# RPi-ShieldBridge_v11.net
KiCad netlist of a schematic drawn in EAGLE
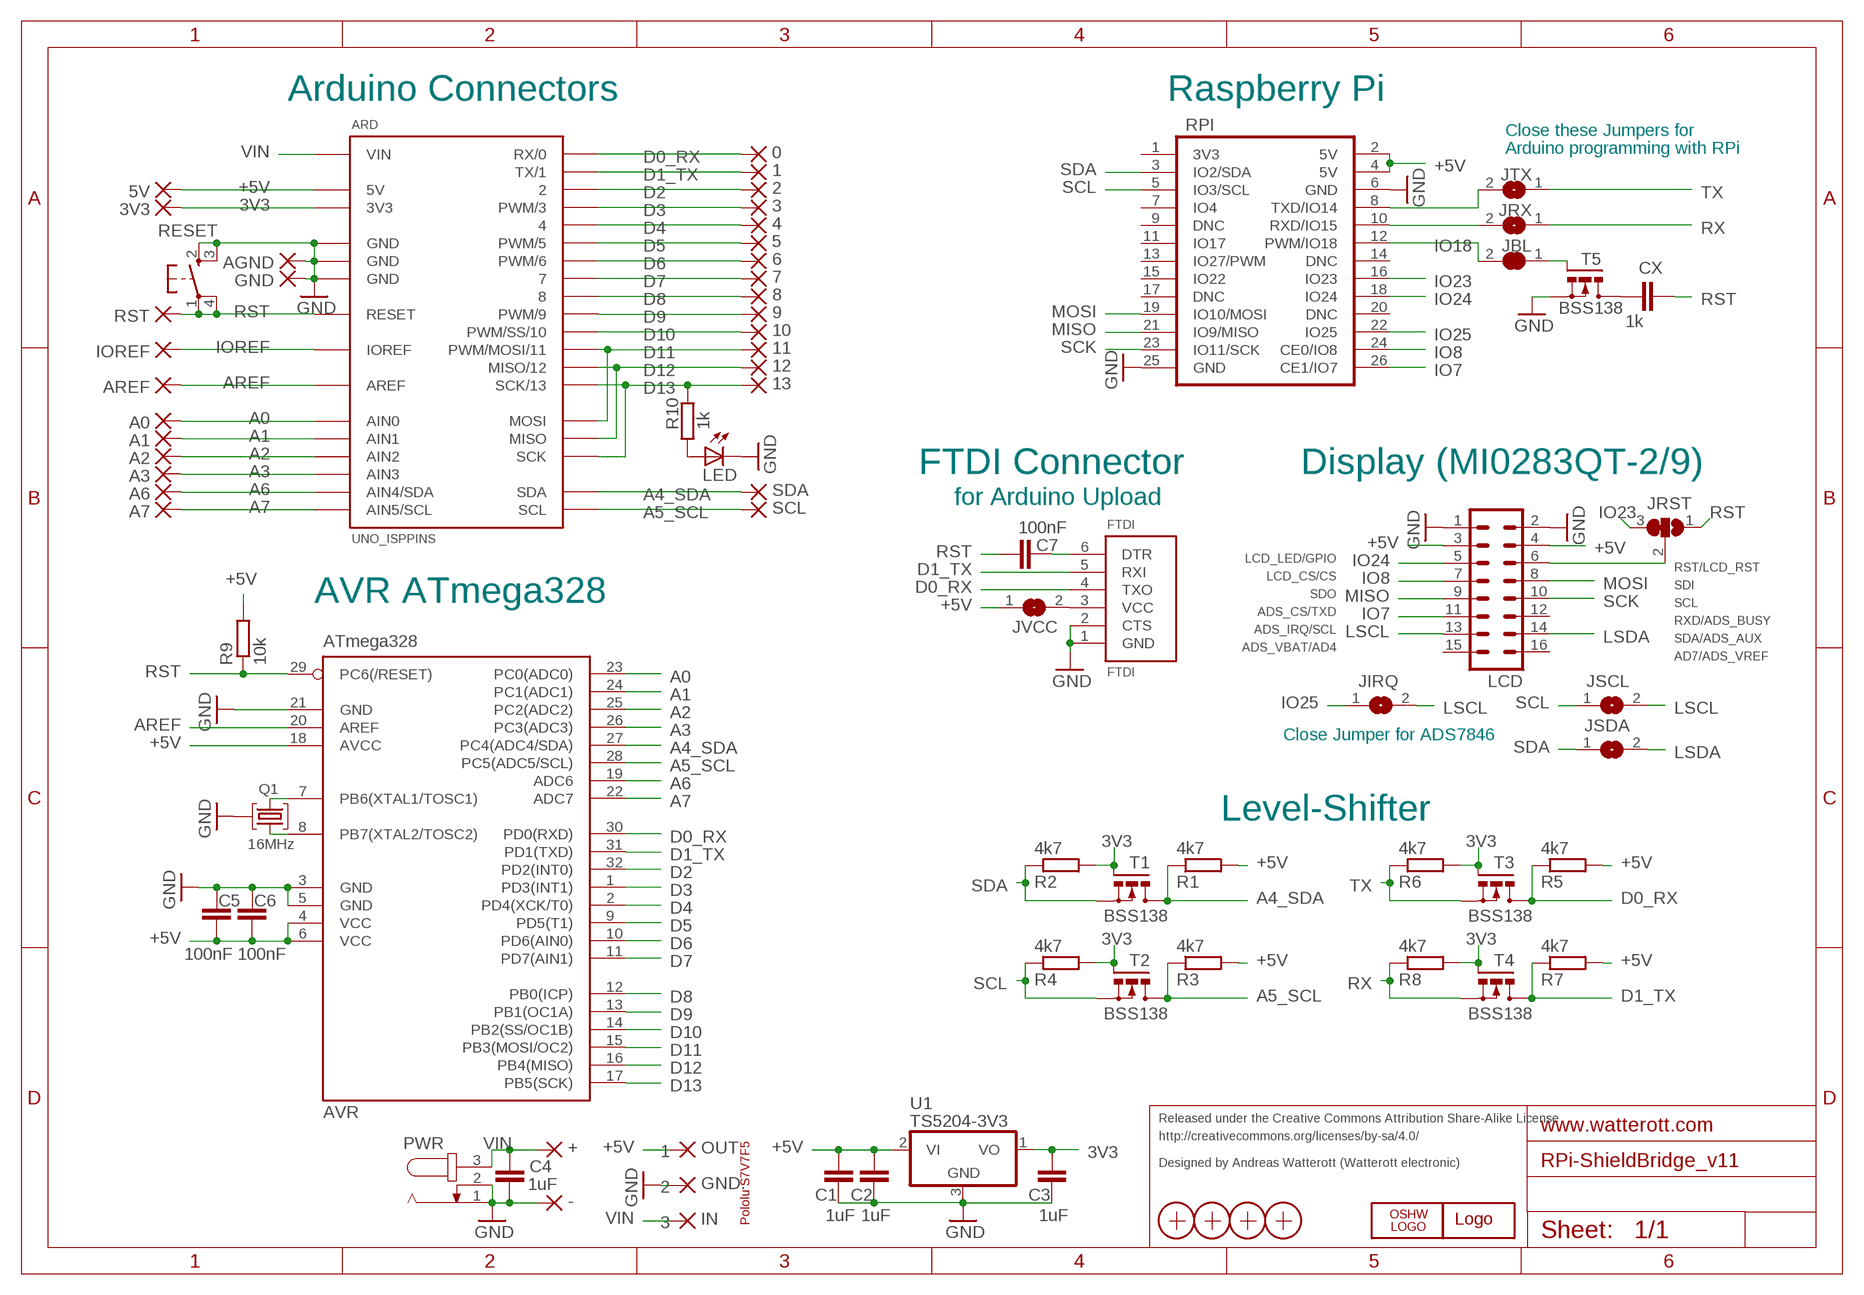
[diagram p0: schematic, sheet 1]

(export (version "E")
  (design (tool "Eeschema 10.0.6"))
  (components
    (comp (ref "+")
      (value "WIREPAD2,54/1,0")
      (footprint "eagle-import:2,54_1,0")
      (libsource (lib "eagle-import") (part "WIREPAD2,54/1,0"))
    )
    (comp (ref "-")
      (value "WIREPAD2,54/1,0")
      (footprint "eagle-import:2,54_1,0")
      (libsource (lib "eagle-import") (part "WIREPAD2,54/1,0"))
    )
    (comp (ref "0")
      (value "WIREPAD1,6/0,9")
      (footprint "eagle-import:1,6_0,9")
      (libsource (lib "eagle-import") (part "WIREPAD1,6/0,9"))
    )
    (comp (ref "1")
      (value "WIREPAD1,6/0,9")
      (footprint "eagle-import:1,6_0,9")
      (libsource (lib "eagle-import") (part "WIREPAD1,6/0,9"))
    )
    (comp (ref "2")
      (value "WIREPAD1,6/0,9")
      (footprint "eagle-import:1,6_0,9")
      (libsource (lib "eagle-import") (part "WIREPAD1,6/0,9"))
    )
    (comp (ref "3")
      (value "WIREPAD1,6/0,9")
      (footprint "eagle-import:1,6_0,9")
      (libsource (lib "eagle-import") (part "WIREPAD1,6/0,9"))
    )
    (comp (ref "3V3")
      (value "WIREPAD1,6/0,9")
      (footprint "eagle-import:1,6_0,9")
      (libsource (lib "eagle-import") (part "WIREPAD1,6/0,9"))
    )
    (comp (ref "4")
      (value "WIREPAD1,6/0,9")
      (footprint "eagle-import:1,6_0,9")
      (libsource (lib "eagle-import") (part "WIREPAD1,6/0,9"))
    )
    (comp (ref "5")
      (value "WIREPAD1,6/0,9")
      (footprint "eagle-import:1,6_0,9")
      (libsource (lib "eagle-import") (part "WIREPAD1,6/0,9"))
    )
    (comp (ref "5V")
      (value "WIREPAD1,6/0,9")
      (footprint "eagle-import:1,6_0,9")
      (libsource (lib "eagle-import") (part "WIREPAD1,6/0,9"))
    )
    (comp (ref "6")
      (value "WIREPAD1,6/0,9")
      (footprint "eagle-import:1,6_0,9")
      (libsource (lib "eagle-import") (part "WIREPAD1,6/0,9"))
    )
    (comp (ref "7")
      (value "WIREPAD1,6/0,9")
      (footprint "eagle-import:1,6_0,9")
      (libsource (lib "eagle-import") (part "WIREPAD1,6/0,9"))
    )
    (comp (ref "8")
      (value "WIREPAD1,6/0,9")
      (footprint "eagle-import:1,6_0,9")
      (libsource (lib "eagle-import") (part "WIREPAD1,6/0,9"))
    )
    (comp (ref "9")
      (value "WIREPAD1,6/0,9")
      (footprint "eagle-import:1,6_0,9")
      (libsource (lib "eagle-import") (part "WIREPAD1,6/0,9"))
    )
    (comp (ref "10")
      (value "WIREPAD1,6/0,9")
      (footprint "eagle-import:1,6_0,9")
      (libsource (lib "eagle-import") (part "WIREPAD1,6/0,9"))
    )
    (comp (ref "11")
      (value "WIREPAD1,6/0,9")
      (footprint "eagle-import:1,6_0,9")
      (libsource (lib "eagle-import") (part "WIREPAD1,6/0,9"))
    )
    (comp (ref "12")
      (value "WIREPAD1,6/0,9")
      (footprint "eagle-import:1,6_0,9")
      (libsource (lib "eagle-import") (part "WIREPAD1,6/0,9"))
    )
    (comp (ref "13")
      (value "WIREPAD1,6/0,9")
      (footprint "eagle-import:1,6_0,9")
      (libsource (lib "eagle-import") (part "WIREPAD1,6/0,9"))
    )
    (comp (ref "A0")
      (value "WIREPAD1,6/0,9")
      (footprint "eagle-import:1,6_0,9")
      (libsource (lib "eagle-import") (part "WIREPAD1,6/0,9"))
    )
    (comp (ref "A1")
      (value "WIREPAD1,6/0,9")
      (footprint "eagle-import:1,6_0,9")
      (libsource (lib "eagle-import") (part "WIREPAD1,6/0,9"))
    )
    (comp (ref "A2")
      (value "WIREPAD1,6/0,9")
      (footprint "eagle-import:1,6_0,9")
      (libsource (lib "eagle-import") (part "WIREPAD1,6/0,9"))
    )
    (comp (ref "A3")
      (value "WIREPAD1,6/0,9")
      (footprint "eagle-import:1,6_0,9")
      (libsource (lib "eagle-import") (part "WIREPAD1,6/0,9"))
    )
    (comp (ref "A6")
      (value "WIREPAD1,6/0,9")
      (footprint "eagle-import:1,6_0,9")
      (libsource (lib "eagle-import") (part "WIREPAD1,6/0,9"))
    )
    (comp (ref "A7")
      (value "WIREPAD1,6/0,9")
      (footprint "eagle-import:1,6_0,9")
      (libsource (lib "eagle-import") (part "WIREPAD1,6/0,9"))
    )
    (comp (ref "AGND")
      (value "WIREPAD1,6/0,9")
      (footprint "eagle-import:1,6_0,9")
      (libsource (lib "eagle-import") (part "WIREPAD1,6/0,9"))
    )
    (comp (ref "ARD")
      (value "UNO_ISPPINS")
      (footprint "eagle-import:UNO_ISP3")
      (libsource (lib "eagle-import") (part "UNO_ISPPINS"))
    )
    (comp (ref "AREF")
      (value "WIREPAD1,6/0,9")
      (footprint "eagle-import:1,6_0,9")
      (libsource (lib "eagle-import") (part "WIREPAD1,6/0,9"))
    )
    (comp (ref "AVR")
      (value "ATmega328")
      (footprint "eagle-import:TQFP32-08")
      (fields (field (name "MPN") "ATMEGA8-16AU"))
      (libsource (lib "eagle-import") (part "MEGA8-AI"))
    )
    (comp (ref "C1")
      (value "1uF")
      (footprint "eagle-import:C0603")
      (libsource (lib "eagle-import") (part "C-EUC0603"))
    )
    (comp (ref "C2")
      (value "1uF")
      (footprint "eagle-import:C0603")
      (libsource (lib "eagle-import") (part "C-EUC0603"))
    )
    (comp (ref "C3")
      (value "1uF")
      (footprint "eagle-import:C0603")
      (libsource (lib "eagle-import") (part "C-EUC0603"))
    )
    (comp (ref "C4")
      (value "1uF")
      (footprint "eagle-import:C0603")
      (libsource (lib "eagle-import") (part "C-EUC0603"))
    )
    (comp (ref "C5")
      (value "100nF")
      (footprint "eagle-import:C0603")
      (libsource (lib "eagle-import") (part "C-EUC0603"))
    )
    (comp (ref "C6")
      (value "100nF")
      (footprint "eagle-import:C0603")
      (libsource (lib "eagle-import") (part "C-EUC0603"))
    )
    (comp (ref "C7")
      (value "100nF")
      (footprint "eagle-import:C0603")
      (libsource (lib "eagle-import") (part "C-EUC0603"))
    )
    (comp (ref "CX")
      (value "1k")
      (footprint "eagle-import:C0603")
      (libsource (lib "eagle-import") (part "C-EUC0603"))
    )
    (comp (ref "FTDI")
      (value "FTDI")
      (footprint "eagle-import:FTDI")
      (libsource (lib "eagle-import") (part "FTDI"))
    )
    (comp (ref "GND")
      (value "WIREPAD1,6/0,9")
      (footprint "eagle-import:1,6_0,9")
      (libsource (lib "eagle-import") (part "WIREPAD1,6/0,9"))
    )
    (comp (ref "GND.")
      (value "2")
      (footprint "eagle-import:1,6_0,9")
      (libsource (lib "eagle-import") (part "WIREPAD1,6/0,9"))
    )
    (comp (ref "IN")
      (value "3")
      (footprint "eagle-import:1,6_0,9")
      (libsource (lib "eagle-import") (part "WIREPAD1,6/0,9"))
    )
    (comp (ref "IOREF")
      (value "WIREPAD1,6/0,9")
      (footprint "eagle-import:1,6_0,9")
      (libsource (lib "eagle-import") (part "WIREPAD1,6/0,9"))
    )
    (comp (ref "JBL") (value "SJ") (footprint "eagle-import:SJ") (libsource (lib "eagle-import") (part "SJ")))
    (comp (ref "JIRQ")
      (value "SJ")
      (footprint "eagle-import:SJ")
      (libsource (lib "eagle-import") (part "SJ"))
    )
    (comp (ref "JRST")
      (value "SJ2W")
      (footprint "eagle-import:SJ_2")
      (libsource (lib "eagle-import") (part "SJ2W"))
    )
    (comp (ref "JRX") (value "SJ") (footprint "eagle-import:SJ") (libsource (lib "eagle-import") (part "SJ")))
    (comp (ref "JSCL")
      (value "SJ")
      (footprint "eagle-import:SJ")
      (libsource (lib "eagle-import") (part "SJ"))
    )
    (comp (ref "JSDA")
      (value "SJ")
      (footprint "eagle-import:SJ")
      (libsource (lib "eagle-import") (part "SJ"))
    )
    (comp (ref "JTX") (value "SJ") (footprint "eagle-import:SJ") (libsource (lib "eagle-import") (part "SJ")))
    (comp (ref "JVCC")
      (value "SJ")
      (footprint "eagle-import:SJ")
      (libsource (lib "eagle-import") (part "SJ"))
    )
    (comp (ref "LCD")
      (value "MA08-2")
      (footprint "eagle-import:MA08-2")
      (libsource (lib "eagle-import") (part "MA08-2"))
    )
    (comp (ref "LED")
      (value "LEDCHIPLED_0603")
      (footprint "eagle-import:CHIPLED_0603")
      (libsource (lib "eagle-import") (part "LEDCHIPLED_0603"))
    )
    (comp (ref "LOGO1")
      (value "OSHW_LOGO_6MILX0150-NT")
      (footprint "eagle-import:OSHW_6X150_NOTEXT")
      (libsource (lib "eagle-import") (part "OSHW_LOGO_6MILX0150-NT"))
    )
    (comp (ref "OUT")
      (value "1")
      (footprint "eagle-import:1,6_0,9")
      (libsource (lib "eagle-import") (part "WIREPAD1,6/0,9"))
    )
    (comp (ref "PWR")
      (value "DC-JACK\"\"")
      (footprint "eagle-import:DC-JACK")
      (libsource (lib "eagle-import") (part "DC-JACK{dblquote}{dblquote}"))
    )
    (comp (ref "Q1")
      (value "16MHz")
      (footprint "eagle-import:SMD_OSC_35X15")
      (libsource (lib "eagle-import") (part "SMD_OSC2"))
    )
    (comp (ref "R1")
      (value "4k7")
      (footprint "eagle-import:R0603")
      (libsource (lib "eagle-import") (part "R-EU_R0603"))
    )
    (comp (ref "R2")
      (value "4k7")
      (footprint "eagle-import:R0603")
      (libsource (lib "eagle-import") (part "R-EU_R0603"))
    )
    (comp (ref "R3")
      (value "4k7")
      (footprint "eagle-import:R0603")
      (libsource (lib "eagle-import") (part "R-EU_R0603"))
    )
    (comp (ref "R4")
      (value "4k7")
      (footprint "eagle-import:R0603")
      (libsource (lib "eagle-import") (part "R-EU_R0603"))
    )
    (comp (ref "R5")
      (value "4k7")
      (footprint "eagle-import:R0603")
      (libsource (lib "eagle-import") (part "R-EU_R0603"))
    )
    (comp (ref "R6")
      (value "4k7")
      (footprint "eagle-import:R0603")
      (libsource (lib "eagle-import") (part "R-EU_R0603"))
    )
    (comp (ref "R7")
      (value "4k7")
      (footprint "eagle-import:R0603")
      (libsource (lib "eagle-import") (part "R-EU_R0603"))
    )
    (comp (ref "R8")
      (value "4k7")
      (footprint "eagle-import:R0603")
      (libsource (lib "eagle-import") (part "R-EU_R0603"))
    )
    (comp (ref "R9")
      (value "10k")
      (footprint "eagle-import:R0603")
      (libsource (lib "eagle-import") (part "R-EU_R0603"))
    )
    (comp (ref "R10")
      (value "1k")
      (footprint "eagle-import:R0603")
      (libsource (lib "eagle-import") (part "R-EU_R0603"))
    )
    (comp (ref "RESET")
      (value "SW_SMDS")
      (footprint "eagle-import:SW_SMD4@1")
      (libsource (lib "eagle-import") (part "SW_SMDS"))
    )
    (comp (ref "RPI")
      (value "RPI")
      (footprint "eagle-import:RPI")
      (libsource (lib "eagle-import") (part "RPI"))
    )
    (comp (ref "RST")
      (value "WIREPAD1,6/0,9")
      (footprint "eagle-import:1,6_0,9")
      (libsource (lib "eagle-import") (part "WIREPAD1,6/0,9"))
    )
    (comp (ref "SCL")
      (value "WIREPAD1,6/0,9")
      (footprint "eagle-import:1,6_0,9")
      (libsource (lib "eagle-import") (part "WIREPAD1,6/0,9"))
    )
    (comp (ref "SDA")
      (value "WIREPAD1,6/0,9")
      (footprint "eagle-import:1,6_0,9")
      (libsource (lib "eagle-import") (part "WIREPAD1,6/0,9"))
    )
    (comp (ref "T1")
      (value "BSS138")
      (footprint "eagle-import:MICRO3")
      (libsource (lib "eagle-import") (part "IRLML2502"))
    )
    (comp (ref "T2")
      (value "BSS138")
      (footprint "eagle-import:MICRO3")
      (libsource (lib "eagle-import") (part "IRLML2502"))
    )
    (comp (ref "T3")
      (value "BSS138")
      (footprint "eagle-import:MICRO3")
      (libsource (lib "eagle-import") (part "IRLML2502"))
    )
    (comp (ref "T4")
      (value "BSS138")
      (footprint "eagle-import:MICRO3")
      (libsource (lib "eagle-import") (part "IRLML2502"))
    )
    (comp (ref "T5")
      (value "BSS138")
      (footprint "eagle-import:MICRO3")
      (libsource (lib "eagle-import") (part "IRLML2502"))
    )
    (comp (ref "U$1")
      (value "WE-LOGO")
      (footprint "eagle-import:WE-LOGO")
      (libsource (lib "eagle-import") (part "WE-LOGOPLACE"))
    )
    (comp (ref "U1")
      (value "TS5204-3V3")
      (footprint "eagle-import:SOT23")
      (libsource (lib "eagle-import") (part "TS5204"))
    )
    (comp (ref "X1")
      (value "PASSER")
      (footprint "eagle-import:PASSER")
      (libsource (lib "eagle-import") (part "PASSER"))
    )
    (comp (ref "X2")
      (value "PASSER")
      (footprint "eagle-import:PASSER")
      (libsource (lib "eagle-import") (part "PASSER"))
    )
    (comp (ref "X3")
      (value "PASSER")
      (footprint "eagle-import:PASSER")
      (libsource (lib "eagle-import") (part "PASSER"))
    )
    (comp (ref "X4")
      (value "PASSER")
      (footprint "eagle-import:PASSER")
      (libsource (lib "eagle-import") (part "PASSER"))
    )
  )
  (nets
    (net (code "1") (name "/+5V") (class "Default")
      (node (ref "5V") (pin "1") (pinfunction "P_1") (pintype "passive"))
      (node (ref "ARD") (pin "5V") (pinfunction "5V_5V") (pintype "power_in"))
      (node (ref "AVR") (pin "18") (pinfunction "AVCC_18") (pintype "power_in"))
      (node (ref "AVR") (pin "4") (pinfunction "VCC_4") (pintype "power_in"))
      (node (ref "AVR") (pin "6") (pinfunction "VCC_6") (pintype "power_in"))
      (node (ref "C1") (pin "1") (pinfunction "1_1") (pintype "passive"))
      (node (ref "C2") (pin "1") (pinfunction "1_1") (pintype "passive"))
      (node (ref "C5") (pin "1") (pinfunction "1_1") (pintype "passive"))
      (node (ref "C6") (pin "1") (pinfunction "1_1") (pintype "passive"))
      (node (ref "JVCC") (pin "1") (pinfunction "1_1") (pintype "passive"))
      (node (ref "LCD") (pin "3") (pinfunction "3_3") (pintype "passive"))
      (node (ref "LCD") (pin "4") (pinfunction "4_4") (pintype "passive"))
      (node (ref "OUT") (pin "1") (pinfunction "P_1") (pintype "passive"))
      (node (ref "R1") (pin "2") (pinfunction "2_2") (pintype "passive"))
      (node (ref "R3") (pin "2") (pinfunction "2_2") (pintype "passive"))
      (node (ref "R5") (pin "2") (pinfunction "2_2") (pintype "passive"))
      (node (ref "R7") (pin "2") (pinfunction "2_2") (pintype "passive"))
      (node (ref "R9") (pin "2") (pinfunction "2_2") (pintype "passive"))
      (node (ref "RPI") (pin "2") (pinfunction "5V_2") (pintype "passive"))
      (node (ref "RPI") (pin "4") (pinfunction "5V_4") (pintype "passive"))
      (node (ref "U1") (pin "2") (pinfunction "VI_2") (pintype "input"))
    )
    (net (code "2") (name "/3V3") (class "Default")
      (node (ref "3V3") (pin "1") (pinfunction "P_1") (pintype "passive"))
      (node (ref "ARD") (pin "3V3") (pinfunction "3V3_3V3") (pintype "power_in"))
      (node (ref "C3") (pin "1") (pinfunction "1_1") (pintype "passive"))
      (node (ref "R2") (pin "2") (pinfunction "2_2") (pintype "passive"))
      (node (ref "R4") (pin "2") (pinfunction "2_2") (pintype "passive"))
      (node (ref "R6") (pin "2") (pinfunction "2_2") (pintype "passive"))
      (node (ref "R8") (pin "2") (pinfunction "2_2") (pintype "passive"))
      (node (ref "T1") (pin "1") (pinfunction "G_1") (pintype "passive"))
      (node (ref "T2") (pin "1") (pinfunction "G_1") (pintype "passive"))
      (node (ref "T3") (pin "1") (pinfunction "G_1") (pintype "passive"))
      (node (ref "T4") (pin "1") (pinfunction "G_1") (pintype "passive"))
      (node (ref "U1") (pin "1") (pinfunction "VO_1") (pintype "passive"))
    )
    (net (code "3") (name "/A0") (class "Default")
      (node (ref "A0") (pin "1") (pinfunction "P_1") (pintype "passive"))
      (node (ref "ARD") (pin "AIN0") (pinfunction "AIN0_AIN0") (pintype "bidirectional"))
      (node (ref "AVR") (pin "23") (pinfunction "PC0(ADC0)_23") (pintype "bidirectional"))
    )
    (net (code "4") (name "/A1") (class "Default")
      (node (ref "A1") (pin "1") (pinfunction "P_1") (pintype "passive"))
      (node (ref "ARD") (pin "AIN1") (pinfunction "AIN1_AIN1") (pintype "bidirectional"))
      (node (ref "AVR") (pin "24") (pinfunction "PC1(ADC1)_24") (pintype "bidirectional"))
    )
    (net (code "5") (name "/A2") (class "Default")
      (node (ref "A2") (pin "1") (pinfunction "P_1") (pintype "passive"))
      (node (ref "ARD") (pin "AIN2") (pinfunction "AIN2_AIN2") (pintype "bidirectional"))
      (node (ref "AVR") (pin "25") (pinfunction "PC2(ADC2)_25") (pintype "bidirectional"))
    )
    (net (code "6") (name "/A3") (class "Default")
      (node (ref "A3") (pin "1") (pinfunction "P_1") (pintype "passive"))
      (node (ref "ARD") (pin "AIN3") (pinfunction "AIN3_AIN3") (pintype "bidirectional"))
      (node (ref "AVR") (pin "26") (pinfunction "PC3(ADC3)_26") (pintype "bidirectional"))
    )
    (net (code "7") (name "/A4_SDA") (class "Default")
      (node (ref "ARD") (pin "SDA") (pinfunction "SDA_SDA") (pintype "bidirectional"))
      (node (ref "AVR") (pin "27") (pinfunction "PC4(ADC4/SDA)_27") (pintype "bidirectional"))
      (node (ref "R1") (pin "1") (pinfunction "1_1") (pintype "passive"))
      (node (ref "SDA") (pin "1") (pinfunction "P_1") (pintype "passive"))
      (node (ref "T1") (pin "3") (pinfunction "D_3") (pintype "passive"))
    )
    (net (code "8") (name "/A5_SCL") (class "Default")
      (node (ref "ARD") (pin "SCL") (pinfunction "SCL_SCL") (pintype "bidirectional"))
      (node (ref "AVR") (pin "28") (pinfunction "PC5(ADC5/SCL)_28") (pintype "bidirectional"))
      (node (ref "R3") (pin "1") (pinfunction "1_1") (pintype "passive"))
      (node (ref "SCL") (pin "1") (pinfunction "P_1") (pintype "passive"))
      (node (ref "T2") (pin "3") (pinfunction "D_3") (pintype "passive"))
    )
    (net (code "9") (name "/A6") (class "Default")
      (node (ref "A6") (pin "1") (pinfunction "P_1") (pintype "passive"))
      (node (ref "ARD") (pin "AIN4") (pinfunction "AIN4/SDA_AIN4") (pintype "bidirectional"))
      (node (ref "AVR") (pin "19") (pinfunction "ADC6_19") (pintype "bidirectional"))
    )
    (net (code "10") (name "/A7") (class "Default")
      (node (ref "A7") (pin "1") (pinfunction "P_1") (pintype "passive"))
      (node (ref "ARD") (pin "AIN5") (pinfunction "AIN5/SCL_AIN5") (pintype "bidirectional"))
      (node (ref "AVR") (pin "22") (pinfunction "ADC7_22") (pintype "bidirectional"))
    )
    (net (code "11") (name "/AREF") (class "Default")
      (node (ref "ARD") (pin "AREF") (pinfunction "AREF_AREF") (pintype "power_in"))
      (node (ref "AREF") (pin "1") (pinfunction "P_1") (pintype "passive"))
      (node (ref "AVR") (pin "20") (pinfunction "AREF_20") (pintype "passive"))
    )
    (net (code "12") (name "/D0_RX") (class "Default")
      (node (ref "0") (pin "1") (pinfunction "P_1") (pintype "passive"))
      (node (ref "ARD") (pin "0") (pinfunction "RX/0_0") (pintype "bidirectional"))
      (node (ref "AVR") (pin "30") (pinfunction "PD0(RXD)_30") (pintype "bidirectional"))
      (node (ref "FTDI") (pin "4") (pinfunction "TXO_4") (pintype "bidirectional"))
      (node (ref "R5") (pin "1") (pinfunction "1_1") (pintype "passive"))
      (node (ref "T3") (pin "3") (pinfunction "D_3") (pintype "passive"))
    )
    (net (code "13") (name "/D1_TX") (class "Default")
      (node (ref "1") (pin "1") (pinfunction "P_1") (pintype "passive"))
      (node (ref "ARD") (pin "1") (pinfunction "TX/1_1") (pintype "bidirectional"))
      (node (ref "AVR") (pin "31") (pinfunction "PD1(TXD)_31") (pintype "bidirectional"))
      (node (ref "FTDI") (pin "5") (pinfunction "RXI_5") (pintype "bidirectional"))
      (node (ref "R7") (pin "1") (pinfunction "1_1") (pintype "passive"))
      (node (ref "T4") (pin "3") (pinfunction "D_3") (pintype "passive"))
    )
    (net (code "14") (name "/D2") (class "Default")
      (node (ref "2") (pin "1") (pinfunction "P_1") (pintype "passive"))
      (node (ref "ARD") (pin "2") (pinfunction "2_2") (pintype "bidirectional"))
      (node (ref "AVR") (pin "32") (pinfunction "PD2(INT0)_32") (pintype "bidirectional"))
    )
    (net (code "15") (name "/D3") (class "Default")
      (node (ref "3") (pin "1") (pinfunction "P_1") (pintype "passive"))
      (node (ref "ARD") (pin "3") (pinfunction "PWM/3_3") (pintype "bidirectional"))
      (node (ref "AVR") (pin "1") (pinfunction "PD3(INT1)_1") (pintype "bidirectional"))
    )
    (net (code "16") (name "/D4") (class "Default")
      (node (ref "4") (pin "1") (pinfunction "P_1") (pintype "passive"))
      (node (ref "ARD") (pin "4") (pinfunction "4_4") (pintype "bidirectional"))
      (node (ref "AVR") (pin "2") (pinfunction "PD4(XCK/T0)_2") (pintype "bidirectional"))
    )
    (net (code "17") (name "/D5") (class "Default")
      (node (ref "5") (pin "1") (pinfunction "P_1") (pintype "passive"))
      (node (ref "ARD") (pin "5") (pinfunction "PWM/5_5") (pintype "bidirectional"))
      (node (ref "AVR") (pin "9") (pinfunction "PD5(T1)_9") (pintype "bidirectional"))
    )
    (net (code "18") (name "/D6") (class "Default")
      (node (ref "6") (pin "1") (pinfunction "P_1") (pintype "passive"))
      (node (ref "ARD") (pin "6") (pinfunction "PWM/6_6") (pintype "bidirectional"))
      (node (ref "AVR") (pin "10") (pinfunction "PD6(AIN0)_10") (pintype "bidirectional"))
    )
    (net (code "19") (name "/D7") (class "Default")
      (node (ref "7") (pin "1") (pinfunction "P_1") (pintype "passive"))
      (node (ref "ARD") (pin "7") (pinfunction "7_7") (pintype "bidirectional"))
      (node (ref "AVR") (pin "11") (pinfunction "PD7(AIN1)_11") (pintype "bidirectional"))
    )
    (net (code "20") (name "/D8") (class "Default")
      (node (ref "8") (pin "1") (pinfunction "P_1") (pintype "passive"))
      (node (ref "ARD") (pin "8") (pinfunction "8_8") (pintype "bidirectional"))
      (node (ref "AVR") (pin "12") (pinfunction "PB0(ICP)_12") (pintype "bidirectional"))
    )
    (net (code "21") (name "/D9") (class "Default")
      (node (ref "9") (pin "1") (pinfunction "P_1") (pintype "passive"))
      (node (ref "ARD") (pin "9") (pinfunction "PWM/9_9") (pintype "bidirectional"))
      (node (ref "AVR") (pin "13") (pinfunction "PB1(OC1A)_13") (pintype "bidirectional"))
    )
    (net (code "22") (name "/D10") (class "Default")
      (node (ref "10") (pin "1") (pinfunction "P_1") (pintype "passive"))
      (node (ref "ARD") (pin "10") (pinfunction "PWM/SS/10_10") (pintype "bidirectional"))
      (node (ref "AVR") (pin "14") (pinfunction "PB2(SS/OC1B)_14") (pintype "bidirectional"))
    )
    (net (code "23") (name "/D11") (class "Default")
      (node (ref "11") (pin "1") (pinfunction "P_1") (pintype "passive"))
      (node (ref "ARD") (pin "11") (pinfunction "PWM/MOSI/11_11") (pintype "bidirectional"))
      (node (ref "ARD") (pin "MOSI") (pinfunction "MOSI_MOSI") (pintype "bidirectional"))
      (node (ref "AVR") (pin "15") (pinfunction "PB3(MOSI/OC2)_15") (pintype "bidirectional"))
    )
    (net (code "24") (name "/D12") (class "Default")
      (node (ref "12") (pin "1") (pinfunction "P_1") (pintype "passive"))
      (node (ref "ARD") (pin "12") (pinfunction "MISO/12_12") (pintype "bidirectional"))
      (node (ref "ARD") (pin "MISO") (pinfunction "MISO_MISO") (pintype "bidirectional"))
      (node (ref "AVR") (pin "16") (pinfunction "PB4(MISO)_16") (pintype "bidirectional"))
    )
    (net (code "25") (name "/D13") (class "Default")
      (node (ref "13") (pin "1") (pinfunction "P_1") (pintype "passive"))
      (node (ref "ARD") (pin "13") (pinfunction "SCK/13_13") (pintype "bidirectional"))
      (node (ref "ARD") (pin "SCK") (pinfunction "SCK_SCK") (pintype "bidirectional"))
      (node (ref "AVR") (pin "17") (pinfunction "PB5(SCK)_17") (pintype "bidirectional"))
      (node (ref "R10") (pin "1") (pinfunction "1_1") (pintype "passive"))
    )
    (net (code "26") (name "/IO7") (class "Default")
      (node (ref "LCD") (pin "11") (pinfunction "11_11") (pintype "passive"))
      (node (ref "RPI") (pin "26") (pinfunction "CE1/IO7_26") (pintype "passive"))
    )
    (net (code "27") (name "/IO8") (class "Default")
      (node (ref "LCD") (pin "7") (pinfunction "7_7") (pintype "passive"))
      (node (ref "RPI") (pin "24") (pinfunction "CE0/IO8_24") (pintype "passive"))
    )
    (net (code "28") (name "/IO18") (class "Default")
      (node (ref "JBL") (pin "2") (pinfunction "2_2") (pintype "passive"))
      (node (ref "RPI") (pin "12") (pinfunction "PWM/IO18_12") (pintype "passive"))
    )
    (net (code "29") (name "/IO23") (class "Default")
      (node (ref "JRST") (pin "3") (pinfunction "3_3") (pintype "passive"))
      (node (ref "RPI") (pin "16") (pinfunction "IO23_16") (pintype "passive"))
    )
    (net (code "30") (name "/IO24") (class "Default")
      (node (ref "LCD") (pin "5") (pinfunction "5_5") (pintype "passive"))
      (node (ref "RPI") (pin "18") (pinfunction "IO24_18") (pintype "passive"))
    )
    (net (code "31") (name "/IO25") (class "Default")
      (node (ref "JIRQ") (pin "1") (pinfunction "1_1") (pintype "passive"))
      (node (ref "RPI") (pin "22") (pinfunction "IO25_22") (pintype "passive"))
    )
    (net (code "32") (name "/IOREF") (class "Default")
      (node (ref "ARD") (pin "IOREF") (pinfunction "IOREF_IOREF") (pintype "power_in"))
      (node (ref "IOREF") (pin "1") (pinfunction "P_1") (pintype "passive"))
    )
    (net (code "33") (name "/LSCL") (class "Default")
      (node (ref "JIRQ") (pin "2") (pinfunction "2_2") (pintype "passive"))
      (node (ref "JSCL") (pin "2") (pinfunction "2_2") (pintype "passive"))
      (node (ref "LCD") (pin "13") (pinfunction "13_13") (pintype "passive"))
    )
    (net (code "34") (name "/LSDA") (class "Default")
      (node (ref "JSDA") (pin "2") (pinfunction "2_2") (pintype "passive"))
      (node (ref "LCD") (pin "14") (pinfunction "14_14") (pintype "passive"))
    )
    (net (code "35") (name "/MISO") (class "Default")
      (node (ref "LCD") (pin "9") (pinfunction "9_9") (pintype "passive"))
      (node (ref "RPI") (pin "21") (pinfunction "IO9/MISO_21") (pintype "passive"))
    )
    (net (code "36") (name "/MOSI") (class "Default")
      (node (ref "LCD") (pin "8") (pinfunction "8_8") (pintype "passive"))
      (node (ref "RPI") (pin "19") (pinfunction "IO10/MOSI_19") (pintype "passive"))
    )
    (net (code "37") (name "/RST") (class "Default")
      (node (ref "ARD") (pin "RST") (pinfunction "RESET_RST") (pintype "bidirectional"))
      (node (ref "AVR") (pin "29") (pinfunction "PC6(/RESET)_29") (pintype "bidirectional"))
      (node (ref "C7") (pin "2") (pinfunction "2_2") (pintype "passive"))
      (node (ref "CX") (pin "2") (pinfunction "2_2") (pintype "passive"))
      (node (ref "JRST") (pin "1") (pinfunction "1_1") (pintype "passive"))
      (node (ref "R9") (pin "1") (pinfunction "1_1") (pintype "passive"))
      (node (ref "RESET") (pin "1") (pinfunction "P_1") (pintype "passive"))
      (node (ref "RESET") (pin "4") (pinfunction "P1_4") (pintype "passive"))
      (node (ref "RST") (pin "1") (pinfunction "P_1") (pintype "passive"))
    )
    (net (code "38") (name "/RX") (class "Default")
      (node (ref "JRX") (pin "1") (pinfunction "1_1") (pintype "passive"))
      (node (ref "R8") (pin "1") (pinfunction "1_1") (pintype "passive"))
      (node (ref "T4") (pin "2") (pinfunction "S_2") (pintype "passive"))
    )
    (net (code "39") (name "/SCK") (class "Default")
      (node (ref "LCD") (pin "10") (pinfunction "10_10") (pintype "passive"))
      (node (ref "RPI") (pin "23") (pinfunction "IO11/SCK_23") (pintype "passive"))
    )
    (net (code "40") (name "/SCL") (class "Default")
      (node (ref "JSCL") (pin "1") (pinfunction "1_1") (pintype "passive"))
      (node (ref "R4") (pin "1") (pinfunction "1_1") (pintype "passive"))
      (node (ref "RPI") (pin "5") (pinfunction "IO3/SCL_5") (pintype "passive"))
      (node (ref "T2") (pin "2") (pinfunction "S_2") (pintype "passive"))
    )
    (net (code "41") (name "/SDA") (class "Default")
      (node (ref "JSDA") (pin "1") (pinfunction "1_1") (pintype "passive"))
      (node (ref "R2") (pin "1") (pinfunction "1_1") (pintype "passive"))
      (node (ref "RPI") (pin "3") (pinfunction "IO2/SDA_3") (pintype "passive"))
      (node (ref "T1") (pin "2") (pinfunction "S_2") (pintype "passive"))
    )
    (net (code "42") (name "/TX") (class "Default")
      (node (ref "JTX") (pin "1") (pinfunction "1_1") (pintype "passive"))
      (node (ref "R6") (pin "1") (pinfunction "1_1") (pintype "passive"))
      (node (ref "T3") (pin "2") (pinfunction "S_2") (pintype "passive"))
    )
    (net (code "43") (name "/VIN") (class "Default")
      (node (ref "+") (pin "1") (pinfunction "P_1") (pintype "passive"))
      (node (ref "ARD") (pin "VIN") (pinfunction "VIN_VIN") (pintype "power_in"))
      (node (ref "C4") (pin "1") (pinfunction "1_1") (pintype "passive"))
      (node (ref "IN") (pin "1") (pinfunction "P_1") (pintype "passive"))
      (node (ref "PWR") (pin "3") (pinfunction "3_3") (pintype "passive"))
    )
    (net (code "44") (name "GND") (class "Default")
      (node (ref "-") (pin "1") (pinfunction "P_1") (pintype "passive"))
      (node (ref "AGND") (pin "1") (pinfunction "P_1") (pintype "passive"))
      (node (ref "ARD") (pin "GND@1") (pinfunction "GND_GND@1") (pintype "power_in"))
      (node (ref "ARD") (pin "GND@2") (pinfunction "GND_GND@2") (pintype "power_in"))
      (node (ref "ARD") (pin "GND@3") (pinfunction "GND_GND@3") (pintype "power_in"))
      (node (ref "AVR") (pin "21") (pinfunction "GND_21") (pintype "power_in"))
      (node (ref "AVR") (pin "3") (pinfunction "GND_3") (pintype "power_in"))
      (node (ref "AVR") (pin "5") (pinfunction "GND_5") (pintype "power_in"))
      (node (ref "C1") (pin "2") (pinfunction "2_2") (pintype "passive"))
      (node (ref "C2") (pin "2") (pinfunction "2_2") (pintype "passive"))
      (node (ref "C3") (pin "2") (pinfunction "2_2") (pintype "passive"))
      (node (ref "C4") (pin "2") (pinfunction "2_2") (pintype "passive"))
      (node (ref "C5") (pin "2") (pinfunction "2_2") (pintype "passive"))
      (node (ref "C6") (pin "2") (pinfunction "2_2") (pintype "passive"))
      (node (ref "FTDI") (pin "1") (pinfunction "GND_1") (pintype "bidirectional"))
      (node (ref "FTDI") (pin "2") (pinfunction "CTS_2") (pintype "bidirectional"))
      (node (ref "GND") (pin "1") (pinfunction "P_1") (pintype "passive"))
      (node (ref "GND.") (pin "1") (pinfunction "P_1") (pintype "passive"))
      (node (ref "LCD") (pin "1") (pinfunction "1_1") (pintype "passive"))
      (node (ref "LCD") (pin "2") (pinfunction "2_2") (pintype "passive"))
      (node (ref "LED") (pin "C") (pinfunction "C_C") (pintype "passive"))
      (node (ref "PWR") (pin "1") (pinfunction "1_1") (pintype "passive"))
      (node (ref "PWR") (pin "2") (pinfunction "2_2") (pintype "passive"))
      (node (ref "Q1") (pin "GND") (pinfunction "GND_GND") (pintype "passive"))
      (node (ref "RESET") (pin "2") (pinfunction "S_2") (pintype "passive"))
      (node (ref "RESET") (pin "3") (pinfunction "S1_3") (pintype "passive"))
      (node (ref "RPI") (pin "25") (pinfunction "GND_25") (pintype "passive"))
      (node (ref "RPI") (pin "6") (pinfunction "GND_6") (pintype "passive"))
      (node (ref "T5") (pin "2") (pinfunction "S_2") (pintype "passive"))
      (node (ref "U1") (pin "3") (pinfunction "GND_3") (pintype "passive"))
    )
    (net (code "45") (name "Net-(AVR-PB6(XTAL1{slash}TOSC1))") (class "Default")
      (node (ref "AVR") (pin "7") (pinfunction "PB6(XTAL1/TOSC1)_7") (pintype "bidirectional"))
      (node (ref "Q1") (pin "1") (pinfunction "1_1") (pintype "passive"))
    )
    (net (code "46") (name "Net-(AVR-PB7(XTAL2{slash}TOSC2))") (class "Default")
      (node (ref "AVR") (pin "8") (pinfunction "PB7(XTAL2/TOSC2)_8") (pintype "bidirectional"))
      (node (ref "Q1") (pin "2") (pinfunction "2_2") (pintype "passive"))
    )
    (net (code "47") (name "Net-(FTDI-DTR)") (class "Default")
      (node (ref "C7") (pin "1") (pinfunction "1_1") (pintype "passive"))
      (node (ref "FTDI") (pin "6") (pinfunction "DTR_6") (pintype "bidirectional"))
    )
    (net (code "48") (name "Net-(FTDI-VCC)") (class "Default")
      (node (ref "FTDI") (pin "3") (pinfunction "VCC_3") (pintype "bidirectional"))
      (node (ref "JVCC") (pin "2") (pinfunction "2_2") (pintype "passive"))
    )
    (net (code "49") (name "Net-(JRST-Pad2)") (class "Default")
      (node (ref "JRST") (pin "2") (pinfunction "2_2") (pintype "passive"))
      (node (ref "LCD") (pin "6") (pinfunction "6_6") (pintype "passive"))
    )
    (net (code "50") (name "Net-(LED-PadA)") (class "Default")
      (node (ref "LED") (pin "A") (pinfunction "A_A") (pintype "passive"))
      (node (ref "R10") (pin "2") (pinfunction "2_2") (pintype "passive"))
    )
    (net (code "51") (name "Net-(RPI-RXD{slash}IO15)") (class "Default")
      (node (ref "JRX") (pin "2") (pinfunction "2_2") (pintype "passive"))
      (node (ref "RPI") (pin "10") (pinfunction "RXD/IO15_10") (pintype "passive"))
    )
    (net (code "52") (name "Net-(RPI-TXD{slash}IO14)") (class "Default")
      (node (ref "JTX") (pin "2") (pinfunction "2_2") (pintype "passive"))
      (node (ref "RPI") (pin "8") (pinfunction "TXD/IO14_8") (pintype "passive"))
    )
    (net (code "53") (name "Net-(T5-D)") (class "Default")
      (node (ref "CX") (pin "1") (pinfunction "1_1") (pintype "passive"))
      (node (ref "T5") (pin "3") (pinfunction "D_3") (pintype "passive"))
    )
    (net (code "54") (name "Net-(T5-G)") (class "Default")
      (node (ref "JBL") (pin "1") (pinfunction "1_1") (pintype "passive"))
      (node (ref "T5") (pin "1") (pinfunction "G_1") (pintype "passive"))
    )
    (net (code "55") (name "unconnected-(LCD-Pad12)") (class "Default")
      (node (ref "LCD") (pin "12") (pinfunction "12_12") (pintype "passive"))
    )
    (net (code "56") (name "unconnected-(LCD-Pad15)") (class "Default")
      (node (ref "LCD") (pin "15") (pinfunction "15_15") (pintype "passive"))
    )
    (net (code "57") (name "unconnected-(LCD-Pad16)") (class "Default")
      (node (ref "LCD") (pin "16") (pinfunction "16_16") (pintype "passive"))
    )
    (net (code "58") (name "unconnected-(RPI-3V3-Pad1)") (class "Default")
      (node (ref "RPI") (pin "1") (pinfunction "3V3_1") (pintype "passive"))
    )
    (net (code "59") (name "unconnected-(RPI-DNC-Pad9)") (class "Default")
      (node (ref "RPI") (pin "9") (pinfunction "DNC_9") (pintype "passive"))
    )
    (net (code "60") (name "unconnected-(RPI-DNC-Pad14)") (class "Default")
      (node (ref "RPI") (pin "14") (pinfunction "DNC_14") (pintype "passive"))
    )
    (net (code "61") (name "unconnected-(RPI-DNC-Pad17)") (class "Default")
      (node (ref "RPI") (pin "17") (pinfunction "DNC_17") (pintype "passive"))
    )
    (net (code "62") (name "unconnected-(RPI-DNC-Pad20)") (class "Default")
      (node (ref "RPI") (pin "20") (pinfunction "DNC_20") (pintype "passive"))
    )
    (net (code "63") (name "unconnected-(RPI-IO4-Pad7)") (class "Default")
      (node (ref "RPI") (pin "7") (pinfunction "IO4_7") (pintype "passive"))
    )
    (net (code "64") (name "unconnected-(RPI-IO17-Pad11)") (class "Default")
      (node (ref "RPI") (pin "11") (pinfunction "IO17_11") (pintype "passive"))
    )
    (net (code "65") (name "unconnected-(RPI-IO22-Pad15)") (class "Default")
      (node (ref "RPI") (pin "15") (pinfunction "IO22_15") (pintype "passive"))
    )
    (net (code "66") (name "unconnected-(RPI-IO27{slash}PWM-Pad13)") (class "Default")
      (node (ref "RPI") (pin "13") (pinfunction "IO27/PWM_13") (pintype "passive"))
    )
  )
)
